# 1sXBusAltimeter.net
KiCad netlist of a schematic drawn in Altium Designer
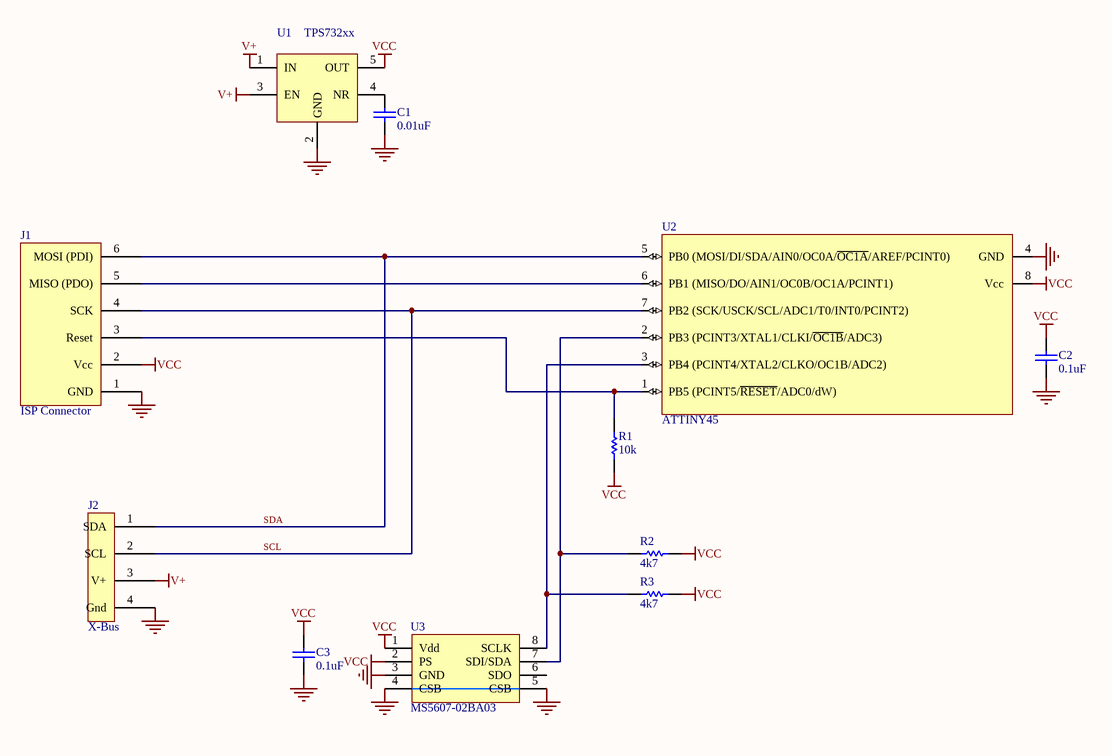
[diagram p0: 1sXBusAltimeter.SchDoc]

(export (version "E")
  (design (tool "Eeschema 10.0.6"))
  (components
    (comp (ref "C1")
      (value "0.01uF")
      (footprint "Cap SMD 0603")
      (description "Capacitor")
      (fields (field (name "Comment") "Cap") (field (name "PUBLISHER") "Altium Limited"))
      (libsource (lib "Custom") (part "Cap"))
    )
    (comp (ref "C2")
      (value "0.1uF")
      (footprint "Cap SMD 0603")
      (description "Capacitor")
      (fields (field (name "Comment") "Cap") (field (name "PUBLISHER") "Altium Limited"))
      (libsource (lib "Custom") (part "Cap"))
    )
    (comp (ref "C3")
      (value "0.1uF")
      (footprint "Cap SMD 0603")
      (description "Capacitor")
      (fields (field (name "Comment") "Cap") (field (name "PUBLISHER") "Altium Limited"))
      (libsource (lib "Custom") (part "Cap"))
    )
    (comp (ref "J1")
      (value "ISP Connector")
      (footprint "Miscellaneous Connector PCB:HDR2X3")
      (libsource (lib "Custom") (part "ISP Connector"))
    )
    (comp (ref "J2")
      (value "X-Bus")
      (footprint "JST-ZH S4B-ZR")
      (libsource (lib "Custom") (part "SIP4 CONNECTOR"))
    )
    (comp (ref "R1")
      (value "10k")
      (footprint "Res SMD 0603")
      (fields (field (name "Comment") "Res1"))
      (libsource (lib "Custom") (part "Resistor"))
    )
    (comp (ref "R2")
      (value "4k7")
      (footprint "Res SMD 0603")
      (fields (field (name "Comment") "Res1"))
      (libsource (lib "Custom") (part "Resistor"))
    )
    (comp (ref "R3")
      (value "4k7")
      (footprint "Res SMD 0603")
      (fields (field (name "Comment") "Res1"))
      (libsource (lib "Custom") (part "Resistor"))
    )
    (comp (ref "U1")
      (value "TPS732xx")
      (footprint "SOT-23-5")
      (description "TPS732xx LDO Voltage Regulator")
      (libsource (lib "Custom") (part "TPS732xx LDO"))
    )
    (comp (ref "U2")
      (value "ATTINY45")
      (footprint "TSSOP8-4.4mm")
      (libsource (lib "Custom") (part "ATTINY45"))
    )
    (comp (ref "U3")
      (value "MS5607-02BA03")
      (footprint "QFN-8")
      (description "MS5607-02BA03 Barometer")
      (libsource (lib "Custom") (part "MS5607-02BA03"))
    )
  )
  (nets
    (net (code "1") (name "/SCL") (class "Default")
      (node (ref "J1") (pin "4") (pinfunction "SCK_4") (pintype "passive"))
      (node (ref "J2") (pin "2") (pinfunction "SCL_2") (pintype "passive"))
      (node (ref "U2") (pin "7") (pinfunction "PB2_(SCK/USCK/SCL/ADC1/T0/INT0/PCINT2)_7") (pintype "bidirectional"))
    )
    (net (code "2") (name "/SDA") (class "Default")
      (node (ref "J1") (pin "6") (pinfunction "MOSI_(PDI)_6") (pintype "passive"))
      (node (ref "J2") (pin "1") (pinfunction "SDA_1") (pintype "passive"))
      (node (ref "U2") (pin "5") (pinfunction "PB0_(MOSI/DI/SDA/AIN0/OC0A/~{OC1A}/AREF/PCINT0)_5") (pintype "bidirectional"))
    )
    (net (code "3") (name "GND") (class "Default")
      (node (ref "C1") (pin "1") (pinfunction "1_1") (pintype "passive"))
      (node (ref "C2") (pin "1") (pinfunction "1_1") (pintype "passive"))
      (node (ref "C3") (pin "1") (pinfunction "1_1") (pintype "passive"))
      (node (ref "J1") (pin "1") (pinfunction "GND_1") (pintype "passive"))
      (node (ref "J2") (pin "4") (pinfunction "Gnd_4") (pintype "passive"))
      (node (ref "U1") (pin "2") (pinfunction "GND_2") (pintype "passive"))
      (node (ref "U2") (pin "4") (pinfunction "GND_4") (pintype "power_in"))
      (node (ref "U3") (pin "3") (pinfunction "GND_3") (pintype "passive"))
      (node (ref "U3") (pin "4") (pinfunction "CSB_4") (pintype "passive"))
      (node (ref "U3") (pin "5") (pinfunction "CSB_5") (pintype "passive"))
    )
    (net (code "4") (name "Net-(J1-MISO_(PDO))") (class "Default")
      (node (ref "J1") (pin "5") (pinfunction "MISO_(PDO)_5") (pintype "passive"))
      (node (ref "U2") (pin "6") (pinfunction "PB1_(MISO/DO/AIN1/OC0B/OC1A/PCINT1)_6") (pintype "bidirectional"))
    )
    (net (code "5") (name "Net-(J1-Reset)") (class "Default")
      (node (ref "J1") (pin "3") (pinfunction "Reset_3") (pintype "passive"))
      (node (ref "R1") (pin "1") (pinfunction "1_1") (pintype "passive"))
      (node (ref "U2") (pin "1") (pinfunction "PB5_(PCINT5/~{RESET}/ADC0/dW)_1") (pintype "bidirectional"))
    )
    (net (code "6") (name "Net-(U1-NR)") (class "Default")
      (node (ref "C1") (pin "2") (pinfunction "2_2") (pintype "passive"))
      (node (ref "U1") (pin "4") (pinfunction "NR_4") (pintype "passive"))
    )
    (net (code "7") (name "Net-(U2-PB3_(PCINT3{slash}XTAL1{slash}CLKI{slash}~{OC1B}{slash}ADC3))") (class "Default")
      (node (ref "R2") (pin "1") (pinfunction "1_1") (pintype "passive"))
      (node (ref "U2") (pin "2") (pinfunction "PB3_(PCINT3/XTAL1/CLKI/~{OC1B}/ADC3)_2") (pintype "bidirectional"))
      (node (ref "U3") (pin "7") (pinfunction "SDI/SDA_7") (pintype "passive"))
    )
    (net (code "8") (name "Net-(U2-PB4_(PCINT4{slash}XTAL2{slash}CLKO{slash}OC1B{slash}ADC2))") (class "Default")
      (node (ref "R3") (pin "1") (pinfunction "1_1") (pintype "passive"))
      (node (ref "U2") (pin "3") (pinfunction "PB4_(PCINT4/XTAL2/CLKO/OC1B/ADC2)_3") (pintype "bidirectional"))
      (node (ref "U3") (pin "8") (pinfunction "SCLK_8") (pintype "passive"))
    )
    (net (code "9") (name "V+") (class "Default")
      (node (ref "J2") (pin "3") (pinfunction "V+_3") (pintype "passive"))
      (node (ref "U1") (pin "1") (pinfunction "IN_1") (pintype "passive"))
      (node (ref "U1") (pin "3") (pinfunction "EN_3") (pintype "passive"))
    )
    (net (code "10") (name "VCC") (class "Default")
      (node (ref "C2") (pin "2") (pinfunction "2_2") (pintype "passive"))
      (node (ref "C3") (pin "2") (pinfunction "2_2") (pintype "passive"))
      (node (ref "J1") (pin "2") (pinfunction "Vcc_2") (pintype "passive"))
      (node (ref "R1") (pin "2") (pinfunction "2_2") (pintype "passive"))
      (node (ref "R2") (pin "2") (pinfunction "2_2") (pintype "passive"))
      (node (ref "R3") (pin "2") (pinfunction "2_2") (pintype "passive"))
      (node (ref "U1") (pin "5") (pinfunction "OUT_5") (pintype "passive"))
      (node (ref "U2") (pin "8") (pinfunction "Vcc_8") (pintype "power_in"))
      (node (ref "U3") (pin "1") (pinfunction "Vdd_1") (pintype "passive"))
      (node (ref "U3") (pin "2") (pinfunction "PS_2") (pintype "passive"))
    )
    (net (code "11") (name "unconnected-(U3-SDO-Pad6)") (class "Default")
      (node (ref "U3") (pin "6") (pinfunction "SDO_6") (pintype "passive"))
    )
  )
)
